# zdroje.net
KiCad netlist of a schematic drawn in EAGLE
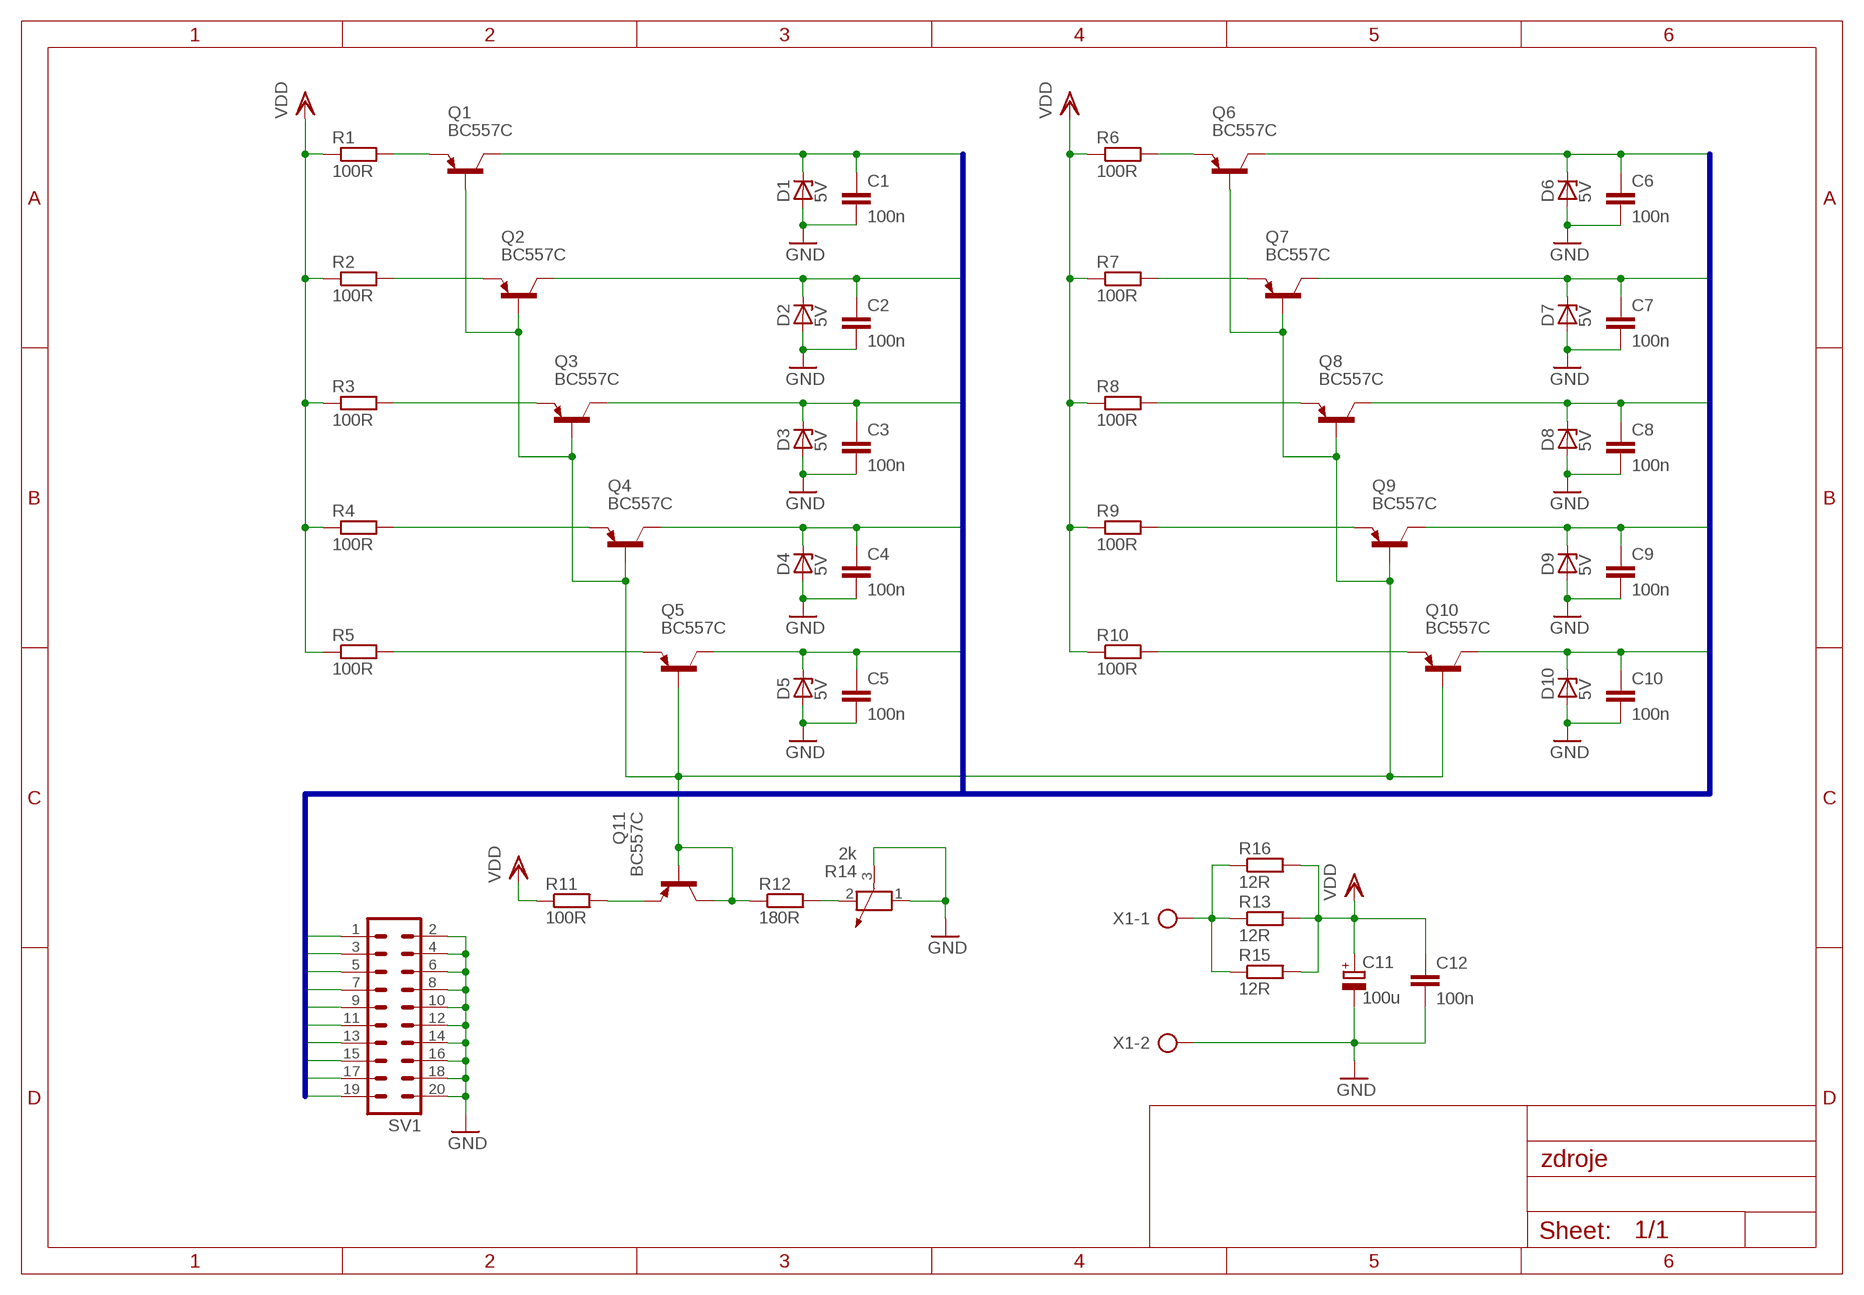
[diagram p0: schematic, sheet 1]

(export (version "E")
  (design (tool "Eeschema 10.0.6"))
  (components
    (comp (ref "C1")
      (value "100n")
      (footprint "eagle-import:C050-030X075")
      (libsource (lib "eagle-import") (part "C-EU050-030X075"))
    )
    (comp (ref "C2")
      (value "100n")
      (footprint "eagle-import:C050-030X075")
      (libsource (lib "eagle-import") (part "C-EU050-030X075"))
    )
    (comp (ref "C3")
      (value "100n")
      (footprint "eagle-import:C050-030X075")
      (libsource (lib "eagle-import") (part "C-EU050-030X075"))
    )
    (comp (ref "C4")
      (value "100n")
      (footprint "eagle-import:C050-030X075")
      (libsource (lib "eagle-import") (part "C-EU050-030X075"))
    )
    (comp (ref "C5")
      (value "100n")
      (footprint "eagle-import:C050-030X075")
      (libsource (lib "eagle-import") (part "C-EU050-030X075"))
    )
    (comp (ref "C6")
      (value "100n")
      (footprint "eagle-import:C050-030X075")
      (libsource (lib "eagle-import") (part "C-EU050-030X075"))
    )
    (comp (ref "C7")
      (value "100n")
      (footprint "eagle-import:C050-030X075")
      (libsource (lib "eagle-import") (part "C-EU050-030X075"))
    )
    (comp (ref "C8")
      (value "100n")
      (footprint "eagle-import:C050-030X075")
      (libsource (lib "eagle-import") (part "C-EU050-030X075"))
    )
    (comp (ref "C9")
      (value "100n")
      (footprint "eagle-import:C050-030X075")
      (libsource (lib "eagle-import") (part "C-EU050-030X075"))
    )
    (comp (ref "C10")
      (value "100n")
      (footprint "eagle-import:C050-030X075")
      (libsource (lib "eagle-import") (part "C-EU050-030X075"))
    )
    (comp (ref "C11")
      (value "100u")
      (footprint "eagle-import:E5-8,5")
      (libsource (lib "eagle-import") (part "CPOL-EUE5-8.5"))
    )
    (comp (ref "C12")
      (value "100n")
      (footprint "eagle-import:C050-030X075")
      (libsource (lib "eagle-import") (part "C-EU050-030X075"))
    )
    (comp (ref "D1")
      (value "5V")
      (footprint "eagle-import:DO35Z10")
      (libsource (lib "eagle-import") (part "ZENER-DIODEDO35Z10"))
    )
    (comp (ref "D2")
      (value "5V")
      (footprint "eagle-import:DO35Z10")
      (libsource (lib "eagle-import") (part "ZENER-DIODEDO35Z10"))
    )
    (comp (ref "D3")
      (value "5V")
      (footprint "eagle-import:DO35Z10")
      (libsource (lib "eagle-import") (part "ZENER-DIODEDO35Z10"))
    )
    (comp (ref "D4")
      (value "5V")
      (footprint "eagle-import:DO35Z10")
      (libsource (lib "eagle-import") (part "ZENER-DIODEDO35Z10"))
    )
    (comp (ref "D5")
      (value "5V")
      (footprint "eagle-import:DO35Z10")
      (libsource (lib "eagle-import") (part "ZENER-DIODEDO35Z10"))
    )
    (comp (ref "D6")
      (value "5V")
      (footprint "eagle-import:DO35Z10")
      (libsource (lib "eagle-import") (part "ZENER-DIODEDO35Z10"))
    )
    (comp (ref "D7")
      (value "5V")
      (footprint "eagle-import:DO35Z10")
      (libsource (lib "eagle-import") (part "ZENER-DIODEDO35Z10"))
    )
    (comp (ref "D8")
      (value "5V")
      (footprint "eagle-import:DO35Z10")
      (libsource (lib "eagle-import") (part "ZENER-DIODEDO35Z10"))
    )
    (comp (ref "D9")
      (value "5V")
      (footprint "eagle-import:DO35Z10")
      (libsource (lib "eagle-import") (part "ZENER-DIODEDO35Z10"))
    )
    (comp (ref "D10")
      (value "5V")
      (footprint "eagle-import:DO35Z10")
      (libsource (lib "eagle-import") (part "ZENER-DIODEDO35Z10"))
    )
    (comp (ref "Q1")
      (value "BC557C")
      (footprint "eagle-import:TO92-EBC")
      (libsource (lib "eagle-import") (part "BC557C"))
    )
    (comp (ref "Q2")
      (value "BC557C")
      (footprint "eagle-import:TO92-EBC")
      (libsource (lib "eagle-import") (part "BC557C"))
    )
    (comp (ref "Q3")
      (value "BC557C")
      (footprint "eagle-import:TO92-EBC")
      (libsource (lib "eagle-import") (part "BC557C"))
    )
    (comp (ref "Q4")
      (value "BC557C")
      (footprint "eagle-import:TO92-EBC")
      (libsource (lib "eagle-import") (part "BC557C"))
    )
    (comp (ref "Q5")
      (value "BC557C")
      (footprint "eagle-import:TO92-EBC")
      (libsource (lib "eagle-import") (part "BC557C"))
    )
    (comp (ref "Q6")
      (value "BC557C")
      (footprint "eagle-import:TO92-EBC")
      (libsource (lib "eagle-import") (part "BC557C"))
    )
    (comp (ref "Q7")
      (value "BC557C")
      (footprint "eagle-import:TO92-EBC")
      (libsource (lib "eagle-import") (part "BC557C"))
    )
    (comp (ref "Q8")
      (value "BC557C")
      (footprint "eagle-import:TO92-EBC")
      (libsource (lib "eagle-import") (part "BC557C"))
    )
    (comp (ref "Q9")
      (value "BC557C")
      (footprint "eagle-import:TO92-EBC")
      (libsource (lib "eagle-import") (part "BC557C"))
    )
    (comp (ref "Q10")
      (value "BC557C")
      (footprint "eagle-import:TO92-EBC")
      (libsource (lib "eagle-import") (part "BC557C"))
    )
    (comp (ref "Q11")
      (value "BC557C")
      (footprint "eagle-import:TO92-EBC")
      (libsource (lib "eagle-import") (part "BC557C"))
    )
    (comp (ref "R1")
      (value "100R")
      (footprint "eagle-import:0207_10")
      (libsource (lib "eagle-import") (part "R-EU_0207/10"))
    )
    (comp (ref "R2")
      (value "100R")
      (footprint "eagle-import:0207_10")
      (libsource (lib "eagle-import") (part "R-EU_0207/10"))
    )
    (comp (ref "R3")
      (value "100R")
      (footprint "eagle-import:0207_10")
      (libsource (lib "eagle-import") (part "R-EU_0207/10"))
    )
    (comp (ref "R4")
      (value "100R")
      (footprint "eagle-import:0207_10")
      (libsource (lib "eagle-import") (part "R-EU_0207/10"))
    )
    (comp (ref "R5")
      (value "100R")
      (footprint "eagle-import:0207_10")
      (libsource (lib "eagle-import") (part "R-EU_0207/10"))
    )
    (comp (ref "R6")
      (value "100R")
      (footprint "eagle-import:0207_10")
      (libsource (lib "eagle-import") (part "R-EU_0207/10"))
    )
    (comp (ref "R7")
      (value "100R")
      (footprint "eagle-import:0207_10")
      (libsource (lib "eagle-import") (part "R-EU_0207/10"))
    )
    (comp (ref "R8")
      (value "100R")
      (footprint "eagle-import:0207_10")
      (libsource (lib "eagle-import") (part "R-EU_0207/10"))
    )
    (comp (ref "R9")
      (value "100R")
      (footprint "eagle-import:0207_10")
      (libsource (lib "eagle-import") (part "R-EU_0207/10"))
    )
    (comp (ref "R10")
      (value "100R")
      (footprint "eagle-import:0207_10")
      (libsource (lib "eagle-import") (part "R-EU_0207/10"))
    )
    (comp (ref "R11")
      (value "100R")
      (footprint "eagle-import:0207_10")
      (libsource (lib "eagle-import") (part "R-EU_0207/10"))
    )
    (comp (ref "R12")
      (value "180R")
      (footprint "eagle-import:0207_10")
      (libsource (lib "eagle-import") (part "R-EU_0207/10"))
    )
    (comp (ref "R13")
      (value "12R")
      (footprint "eagle-import:0207_10")
      (libsource (lib "eagle-import") (part "R-EU_0207/10"))
    )
    (comp (ref "R14")
      (value "2k")
      (footprint "eagle-import:PT-SPIN")
      (libsource (lib "eagle-import") (part "POTENTIOMETER_PT_SPIN"))
    )
    (comp (ref "R15")
      (value "12R")
      (footprint "eagle-import:0207_10")
      (libsource (lib "eagle-import") (part "R-EU_0207/10"))
    )
    (comp (ref "R16")
      (value "12R")
      (footprint "eagle-import:0207_10")
      (libsource (lib "eagle-import") (part "R-EU_0207/10"))
    )
    (comp (ref "SV1")
      (value "MA10-2")
      (footprint "eagle-import:MA10-2")
      (libsource (lib "eagle-import") (part "MA10-2"))
    )
    (comp (ref "X1")
      (value "AK300/2")
      (footprint "eagle-import:AK300_2")
      (libsource (lib "eagle-import") (part "AK300/2"))
    )
  )
  (nets
    (net (code "1") (name "/I1") (class "Default")
      (node (ref "C1") (pin "1") (pinfunction "1_1") (pintype "passive"))
      (node (ref "D1") (pin "C") (pinfunction "C_C") (pintype "passive"))
      (node (ref "Q1") (pin "C") (pinfunction "C_C") (pintype "passive"))
      (node (ref "SV1") (pin "1") (pinfunction "1_1") (pintype "passive"))
    )
    (net (code "2") (name "/I2") (class "Default")
      (node (ref "C2") (pin "1") (pinfunction "1_1") (pintype "passive"))
      (node (ref "D2") (pin "C") (pinfunction "C_C") (pintype "passive"))
      (node (ref "Q2") (pin "C") (pinfunction "C_C") (pintype "passive"))
      (node (ref "SV1") (pin "3") (pinfunction "3_3") (pintype "passive"))
    )
    (net (code "3") (name "/I3") (class "Default")
      (node (ref "C3") (pin "1") (pinfunction "1_1") (pintype "passive"))
      (node (ref "D3") (pin "C") (pinfunction "C_C") (pintype "passive"))
      (node (ref "Q3") (pin "C") (pinfunction "C_C") (pintype "passive"))
      (node (ref "SV1") (pin "5") (pinfunction "5_5") (pintype "passive"))
    )
    (net (code "4") (name "/I4") (class "Default")
      (node (ref "C4") (pin "1") (pinfunction "1_1") (pintype "passive"))
      (node (ref "D4") (pin "C") (pinfunction "C_C") (pintype "passive"))
      (node (ref "Q4") (pin "C") (pinfunction "C_C") (pintype "passive"))
      (node (ref "SV1") (pin "7") (pinfunction "7_7") (pintype "passive"))
    )
    (net (code "5") (name "/I5") (class "Default")
      (node (ref "C5") (pin "1") (pinfunction "1_1") (pintype "passive"))
      (node (ref "D5") (pin "C") (pinfunction "C_C") (pintype "passive"))
      (node (ref "Q5") (pin "C") (pinfunction "C_C") (pintype "passive"))
      (node (ref "SV1") (pin "9") (pinfunction "9_9") (pintype "passive"))
    )
    (net (code "6") (name "/I6") (class "Default")
      (node (ref "C6") (pin "1") (pinfunction "1_1") (pintype "passive"))
      (node (ref "D6") (pin "C") (pinfunction "C_C") (pintype "passive"))
      (node (ref "Q6") (pin "C") (pinfunction "C_C") (pintype "passive"))
      (node (ref "SV1") (pin "11") (pinfunction "11_11") (pintype "passive"))
    )
    (net (code "7") (name "/I7") (class "Default")
      (node (ref "C7") (pin "1") (pinfunction "1_1") (pintype "passive"))
      (node (ref "D7") (pin "C") (pinfunction "C_C") (pintype "passive"))
      (node (ref "Q7") (pin "C") (pinfunction "C_C") (pintype "passive"))
      (node (ref "SV1") (pin "13") (pinfunction "13_13") (pintype "passive"))
    )
    (net (code "8") (name "/I8") (class "Default")
      (node (ref "C8") (pin "1") (pinfunction "1_1") (pintype "passive"))
      (node (ref "D8") (pin "C") (pinfunction "C_C") (pintype "passive"))
      (node (ref "Q8") (pin "C") (pinfunction "C_C") (pintype "passive"))
      (node (ref "SV1") (pin "15") (pinfunction "15_15") (pintype "passive"))
    )
    (net (code "9") (name "/I9") (class "Default")
      (node (ref "C9") (pin "1") (pinfunction "1_1") (pintype "passive"))
      (node (ref "D9") (pin "C") (pinfunction "C_C") (pintype "passive"))
      (node (ref "Q9") (pin "C") (pinfunction "C_C") (pintype "passive"))
      (node (ref "SV1") (pin "17") (pinfunction "17_17") (pintype "passive"))
    )
    (net (code "10") (name "/I10") (class "Default")
      (node (ref "C10") (pin "1") (pinfunction "1_1") (pintype "passive"))
      (node (ref "D10") (pin "C") (pinfunction "C_C") (pintype "passive"))
      (node (ref "Q10") (pin "C") (pinfunction "C_C") (pintype "passive"))
      (node (ref "SV1") (pin "19") (pinfunction "19_19") (pintype "passive"))
    )
    (net (code "11") (name "GND") (class "Default")
      (node (ref "C1") (pin "2") (pinfunction "2_2") (pintype "passive"))
      (node (ref "C10") (pin "2") (pinfunction "2_2") (pintype "passive"))
      (node (ref "C11") (pin "-") (pinfunction "-_-") (pintype "passive"))
      (node (ref "C12") (pin "2") (pinfunction "2_2") (pintype "passive"))
      (node (ref "C2") (pin "2") (pinfunction "2_2") (pintype "passive"))
      (node (ref "C3") (pin "2") (pinfunction "2_2") (pintype "passive"))
      (node (ref "C4") (pin "2") (pinfunction "2_2") (pintype "passive"))
      (node (ref "C5") (pin "2") (pinfunction "2_2") (pintype "passive"))
      (node (ref "C6") (pin "2") (pinfunction "2_2") (pintype "passive"))
      (node (ref "C7") (pin "2") (pinfunction "2_2") (pintype "passive"))
      (node (ref "C8") (pin "2") (pinfunction "2_2") (pintype "passive"))
      (node (ref "C9") (pin "2") (pinfunction "2_2") (pintype "passive"))
      (node (ref "D1") (pin "A") (pinfunction "A_A") (pintype "passive"))
      (node (ref "D10") (pin "A") (pinfunction "A_A") (pintype "passive"))
      (node (ref "D2") (pin "A") (pinfunction "A_A") (pintype "passive"))
      (node (ref "D3") (pin "A") (pinfunction "A_A") (pintype "passive"))
      (node (ref "D4") (pin "A") (pinfunction "A_A") (pintype "passive"))
      (node (ref "D5") (pin "A") (pinfunction "A_A") (pintype "passive"))
      (node (ref "D6") (pin "A") (pinfunction "A_A") (pintype "passive"))
      (node (ref "D7") (pin "A") (pinfunction "A_A") (pintype "passive"))
      (node (ref "D8") (pin "A") (pinfunction "A_A") (pintype "passive"))
      (node (ref "D9") (pin "A") (pinfunction "A_A") (pintype "passive"))
      (node (ref "R14") (pin "1") (pinfunction "1_1") (pintype "passive"))
      (node (ref "R14") (pin "3") (pinfunction "3_3") (pintype "passive"))
      (node (ref "SV1") (pin "10") (pinfunction "10_10") (pintype "passive"))
      (node (ref "SV1") (pin "12") (pinfunction "12_12") (pintype "passive"))
      (node (ref "SV1") (pin "14") (pinfunction "14_14") (pintype "passive"))
      (node (ref "SV1") (pin "16") (pinfunction "16_16") (pintype "passive"))
      (node (ref "SV1") (pin "18") (pinfunction "18_18") (pintype "passive"))
      (node (ref "SV1") (pin "2") (pinfunction "2_2") (pintype "passive"))
      (node (ref "SV1") (pin "20") (pinfunction "20_20") (pintype "passive"))
      (node (ref "SV1") (pin "4") (pinfunction "4_4") (pintype "passive"))
      (node (ref "SV1") (pin "6") (pinfunction "6_6") (pintype "passive"))
      (node (ref "SV1") (pin "8") (pinfunction "8_8") (pintype "passive"))
      (node (ref "X1") (pin "2") (pinfunction "KL_2") (pintype "passive"))
    )
    (net (code "12") (name "Net-(Q1-PadB)") (class "Default")
      (node (ref "Q1") (pin "B") (pinfunction "B_B") (pintype "passive"))
      (node (ref "Q10") (pin "B") (pinfunction "B_B") (pintype "passive"))
      (node (ref "Q11") (pin "B") (pinfunction "B_B") (pintype "passive"))
      (node (ref "Q11") (pin "C") (pinfunction "C_C") (pintype "passive"))
      (node (ref "Q2") (pin "B") (pinfunction "B_B") (pintype "passive"))
      (node (ref "Q3") (pin "B") (pinfunction "B_B") (pintype "passive"))
      (node (ref "Q4") (pin "B") (pinfunction "B_B") (pintype "passive"))
      (node (ref "Q5") (pin "B") (pinfunction "B_B") (pintype "passive"))
      (node (ref "Q6") (pin "B") (pinfunction "B_B") (pintype "passive"))
      (node (ref "Q7") (pin "B") (pinfunction "B_B") (pintype "passive"))
      (node (ref "Q8") (pin "B") (pinfunction "B_B") (pintype "passive"))
      (node (ref "Q9") (pin "B") (pinfunction "B_B") (pintype "passive"))
      (node (ref "R12") (pin "1") (pinfunction "1_1") (pintype "passive"))
    )
    (net (code "13") (name "Net-(Q1-PadE)") (class "Default")
      (node (ref "Q1") (pin "E") (pinfunction "E_E") (pintype "passive"))
      (node (ref "R1") (pin "2") (pinfunction "2_2") (pintype "passive"))
    )
    (net (code "14") (name "Net-(Q2-PadE)") (class "Default")
      (node (ref "Q2") (pin "E") (pinfunction "E_E") (pintype "passive"))
      (node (ref "R2") (pin "2") (pinfunction "2_2") (pintype "passive"))
    )
    (net (code "15") (name "Net-(Q3-PadE)") (class "Default")
      (node (ref "Q3") (pin "E") (pinfunction "E_E") (pintype "passive"))
      (node (ref "R3") (pin "2") (pinfunction "2_2") (pintype "passive"))
    )
    (net (code "16") (name "Net-(Q4-PadE)") (class "Default")
      (node (ref "Q4") (pin "E") (pinfunction "E_E") (pintype "passive"))
      (node (ref "R4") (pin "2") (pinfunction "2_2") (pintype "passive"))
    )
    (net (code "17") (name "Net-(Q5-PadE)") (class "Default")
      (node (ref "Q5") (pin "E") (pinfunction "E_E") (pintype "passive"))
      (node (ref "R5") (pin "2") (pinfunction "2_2") (pintype "passive"))
    )
    (net (code "18") (name "Net-(Q6-PadE)") (class "Default")
      (node (ref "Q6") (pin "E") (pinfunction "E_E") (pintype "passive"))
      (node (ref "R6") (pin "2") (pinfunction "2_2") (pintype "passive"))
    )
    (net (code "19") (name "Net-(Q7-PadE)") (class "Default")
      (node (ref "Q7") (pin "E") (pinfunction "E_E") (pintype "passive"))
      (node (ref "R7") (pin "2") (pinfunction "2_2") (pintype "passive"))
    )
    (net (code "20") (name "Net-(Q8-PadE)") (class "Default")
      (node (ref "Q8") (pin "E") (pinfunction "E_E") (pintype "passive"))
      (node (ref "R8") (pin "2") (pinfunction "2_2") (pintype "passive"))
    )
    (net (code "21") (name "Net-(Q9-PadE)") (class "Default")
      (node (ref "Q9") (pin "E") (pinfunction "E_E") (pintype "passive"))
      (node (ref "R9") (pin "2") (pinfunction "2_2") (pintype "passive"))
    )
    (net (code "22") (name "Net-(Q10-PadE)") (class "Default")
      (node (ref "Q10") (pin "E") (pinfunction "E_E") (pintype "passive"))
      (node (ref "R10") (pin "2") (pinfunction "2_2") (pintype "passive"))
    )
    (net (code "23") (name "Net-(Q11-PadE)") (class "Default")
      (node (ref "Q11") (pin "E") (pinfunction "E_E") (pintype "passive"))
      (node (ref "R11") (pin "2") (pinfunction "2_2") (pintype "passive"))
    )
    (net (code "24") (name "Net-(R12-Pad2)") (class "Default")
      (node (ref "R12") (pin "2") (pinfunction "2_2") (pintype "passive"))
      (node (ref "R14") (pin "2") (pinfunction "2_2") (pintype "passive"))
    )
    (net (code "25") (name "Net-(X1A-KL)") (class "Default")
      (node (ref "R13") (pin "1") (pinfunction "1_1") (pintype "passive"))
      (node (ref "R15") (pin "1") (pinfunction "1_1") (pintype "passive"))
      (node (ref "R16") (pin "1") (pinfunction "1_1") (pintype "passive"))
      (node (ref "X1") (pin "1") (pinfunction "KL_1") (pintype "passive"))
    )
    (net (code "26") (name "VDD") (class "Default")
      (node (ref "C11") (pin "+") (pinfunction "+_+") (pintype "passive"))
      (node (ref "C12") (pin "1") (pinfunction "1_1") (pintype "passive"))
      (node (ref "R1") (pin "1") (pinfunction "1_1") (pintype "passive"))
      (node (ref "R10") (pin "1") (pinfunction "1_1") (pintype "passive"))
      (node (ref "R11") (pin "1") (pinfunction "1_1") (pintype "passive"))
      (node (ref "R13") (pin "2") (pinfunction "2_2") (pintype "passive"))
      (node (ref "R15") (pin "2") (pinfunction "2_2") (pintype "passive"))
      (node (ref "R16") (pin "2") (pinfunction "2_2") (pintype "passive"))
      (node (ref "R2") (pin "1") (pinfunction "1_1") (pintype "passive"))
      (node (ref "R3") (pin "1") (pinfunction "1_1") (pintype "passive"))
      (node (ref "R4") (pin "1") (pinfunction "1_1") (pintype "passive"))
      (node (ref "R5") (pin "1") (pinfunction "1_1") (pintype "passive"))
      (node (ref "R6") (pin "1") (pinfunction "1_1") (pintype "passive"))
      (node (ref "R7") (pin "1") (pinfunction "1_1") (pintype "passive"))
      (node (ref "R8") (pin "1") (pinfunction "1_1") (pintype "passive"))
      (node (ref "R9") (pin "1") (pinfunction "1_1") (pintype "passive"))
    )
  )
)
